# Encoder.net
KiCad netlist of a schematic drawn in EAGLE
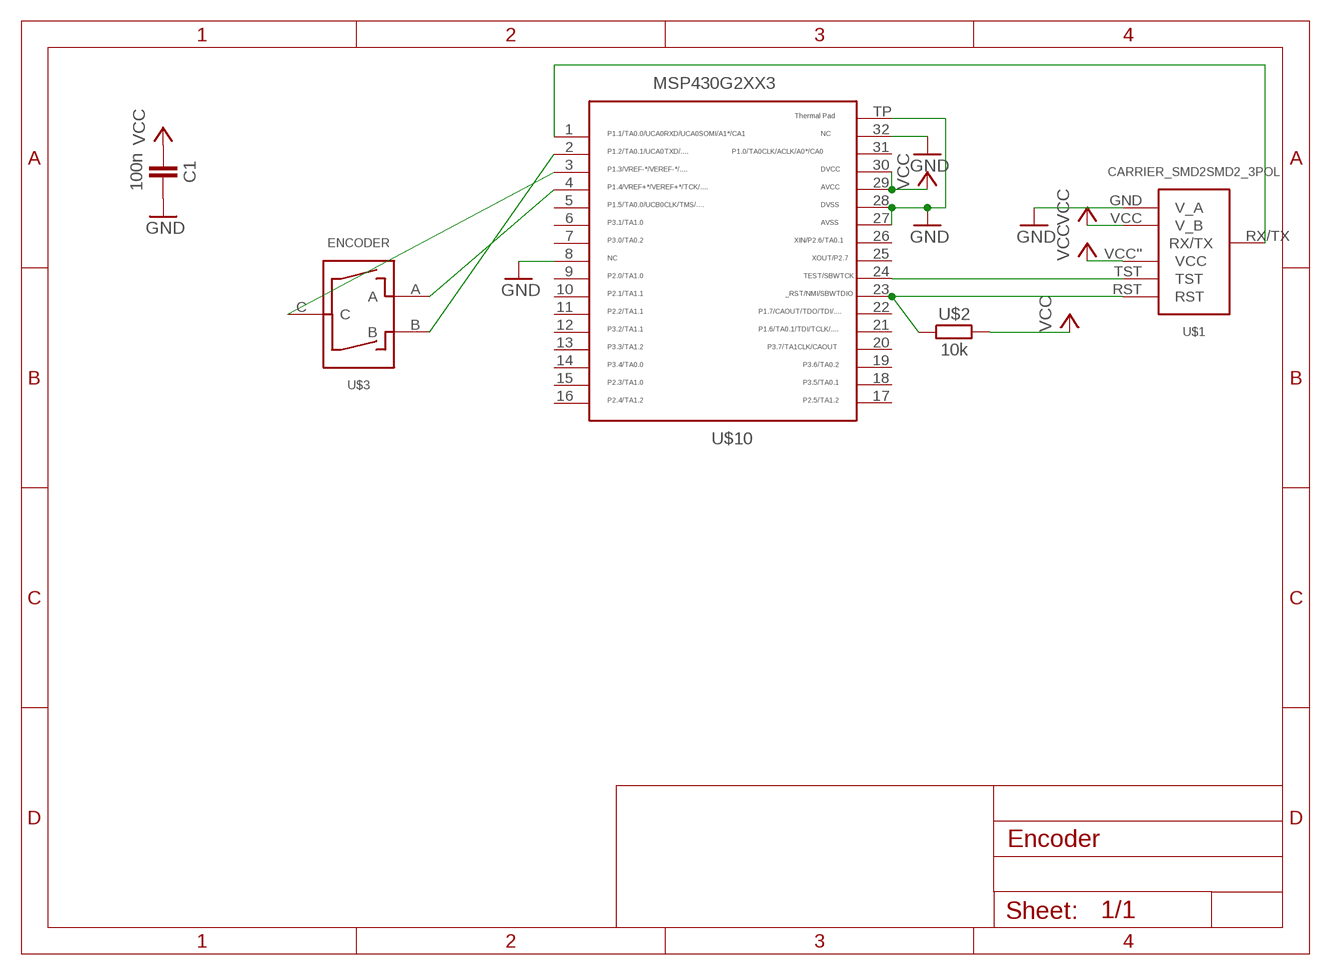
[diagram p0: schematic, sheet 1]

(export (version "E")
  (design (tool "Eeschema 10.0.6"))
  (components
    (comp (ref "C1")
      (value "100n")
      (footprint "eagle-import:603")
      (libsource (lib "eagle-import") (part "CAPACITOR"))
    )
    (comp (ref "U$1")
      (value "CARRIER_SMD2SMD2_3POL")
      (footprint "eagle-import:CARRIER_SMD2_3POL")
      (libsource (lib "eagle-import") (part "CARRIER_SMD2SMD2_3POL"))
    )
    (comp (ref "U$2")
      (value "10k")
      (footprint "eagle-import:603")
      (libsource (lib "eagle-import") (part "RESISTOR0603"))
    )
    (comp (ref "U$3")
      (value "ENCODER")
      (footprint "eagle-import:EC05E")
      (libsource (lib "eagle-import") (part "ENCODER"))
    )
    (comp (ref "U$10")
      (value "MSP430G2553")
      (footprint "eagle-import:QFN32")
      (libsource (lib "eagle-import") (part "MSP430G2553"))
    )
  )
  (nets
    (net (code "1") (name "GND") (class "Default")
      (node (ref "C1") (pin "2") (pinfunction "2_2") (pintype "passive"))
      (node (ref "U$1") (pin "GND") (pinfunction "V_A_GND") (pintype "bidirectional"))
      (node (ref "U$10") (pin "27") (pinfunction "27_27") (pintype "bidirectional"))
      (node (ref "U$10") (pin "28") (pinfunction "28_28") (pintype "bidirectional"))
      (node (ref "U$10") (pin "32") (pinfunction "32_32") (pintype "bidirectional"))
      (node (ref "U$10") (pin "8") (pinfunction "8_8") (pintype "bidirectional"))
      (node (ref "U$10") (pin "TP") (pinfunction "TP_TP") (pintype "bidirectional"))
    )
    (net (code "2") (name "Net-(U$1-PadRST)") (class "Default")
      (node (ref "U$1") (pin "RST") (pinfunction "RST_RST") (pintype "bidirectional"))
      (node (ref "U$10") (pin "23") (pinfunction "23_23") (pintype "bidirectional"))
      (node (ref "U$2") (pin "1") (pinfunction "1_1") (pintype "passive"))
    )
    (net (code "3") (name "Net-(U$1-PadRX{slash}TX)") (class "Default")
      (node (ref "U$1") (pin "RX/TX") (pinfunction "RX/TX_RX/TX") (pintype "bidirectional"))
      (node (ref "U$10") (pin "1") (pinfunction "1_1") (pintype "bidirectional"))
    )
    (net (code "4") (name "Net-(U$1-PadTST)") (class "Default")
      (node (ref "U$1") (pin "TST") (pinfunction "TST_TST") (pintype "bidirectional"))
      (node (ref "U$10") (pin "24") (pinfunction "24_24") (pintype "bidirectional"))
    )
    (net (code "5") (name "Net-(U$10-Pad2)") (class "Default")
      (node (ref "U$10") (pin "2") (pinfunction "2_2") (pintype "bidirectional"))
      (node (ref "U$3") (pin "B") (pinfunction "B_B") (pintype "bidirectional"))
    )
    (net (code "6") (name "Net-(U$10-Pad3)") (class "Default")
      (node (ref "U$10") (pin "3") (pinfunction "3_3") (pintype "bidirectional"))
      (node (ref "U$3") (pin "C") (pinfunction "C_C") (pintype "bidirectional"))
    )
    (net (code "7") (name "Net-(U$10-Pad4)") (class "Default")
      (node (ref "U$10") (pin "4") (pinfunction "4_4") (pintype "bidirectional"))
      (node (ref "U$3") (pin "A") (pinfunction "A_A") (pintype "bidirectional"))
    )
    (net (code "8") (name "VCC") (class "Default")
      (node (ref "C1") (pin "1") (pinfunction "1_1") (pintype "passive"))
      (node (ref "U$1") (pin "VCC") (pinfunction "V_B_VCC") (pintype "bidirectional"))
      (node (ref "U$1") (pin "VCC''") (pinfunction "VCC_VCC''") (pintype "bidirectional"))
      (node (ref "U$10") (pin "29") (pinfunction "29_29") (pintype "bidirectional"))
      (node (ref "U$10") (pin "30") (pinfunction "30_30") (pintype "bidirectional"))
      (node (ref "U$2") (pin "2") (pinfunction "2_2") (pintype "passive"))
    )
    (net (code "9") (name "unconnected-(U$10-Pad5)") (class "Default")
      (node (ref "U$10") (pin "5") (pinfunction "5_5") (pintype "bidirectional"))
    )
    (net (code "10") (name "unconnected-(U$10-Pad6)") (class "Default")
      (node (ref "U$10") (pin "6") (pinfunction "6_6") (pintype "bidirectional"))
    )
    (net (code "11") (name "unconnected-(U$10-Pad7)") (class "Default")
      (node (ref "U$10") (pin "7") (pinfunction "7_7") (pintype "bidirectional"))
    )
    (net (code "12") (name "unconnected-(U$10-Pad9)") (class "Default")
      (node (ref "U$10") (pin "9") (pinfunction "9_9") (pintype "bidirectional"))
    )
    (net (code "13") (name "unconnected-(U$10-Pad10)") (class "Default")
      (node (ref "U$10") (pin "10") (pinfunction "10_10") (pintype "bidirectional"))
    )
    (net (code "14") (name "unconnected-(U$10-Pad11)") (class "Default")
      (node (ref "U$10") (pin "11") (pinfunction "11_11") (pintype "bidirectional"))
    )
    (net (code "15") (name "unconnected-(U$10-Pad12)") (class "Default")
      (node (ref "U$10") (pin "12") (pinfunction "12_12") (pintype "bidirectional"))
    )
    (net (code "16") (name "unconnected-(U$10-Pad13)") (class "Default")
      (node (ref "U$10") (pin "13") (pinfunction "13_13") (pintype "bidirectional"))
    )
    (net (code "17") (name "unconnected-(U$10-Pad14)") (class "Default")
      (node (ref "U$10") (pin "14") (pinfunction "14_14") (pintype "bidirectional"))
    )
    (net (code "18") (name "unconnected-(U$10-Pad15)") (class "Default")
      (node (ref "U$10") (pin "15") (pinfunction "15_15") (pintype "bidirectional"))
    )
    (net (code "19") (name "unconnected-(U$10-Pad16)") (class "Default")
      (node (ref "U$10") (pin "16") (pinfunction "16_16") (pintype "bidirectional"))
    )
    (net (code "20") (name "unconnected-(U$10-Pad17)") (class "Default")
      (node (ref "U$10") (pin "17") (pinfunction "17_17") (pintype "bidirectional"))
    )
    (net (code "21") (name "unconnected-(U$10-Pad18)") (class "Default")
      (node (ref "U$10") (pin "18") (pinfunction "18_18") (pintype "bidirectional"))
    )
    (net (code "22") (name "unconnected-(U$10-Pad19)") (class "Default")
      (node (ref "U$10") (pin "19") (pinfunction "19_19") (pintype "bidirectional"))
    )
    (net (code "23") (name "unconnected-(U$10-Pad20)") (class "Default")
      (node (ref "U$10") (pin "20") (pinfunction "20_20") (pintype "bidirectional"))
    )
    (net (code "24") (name "unconnected-(U$10-Pad21)") (class "Default")
      (node (ref "U$10") (pin "21") (pinfunction "21_21") (pintype "bidirectional"))
    )
    (net (code "25") (name "unconnected-(U$10-Pad22)") (class "Default")
      (node (ref "U$10") (pin "22") (pinfunction "22_22") (pintype "bidirectional"))
    )
    (net (code "26") (name "unconnected-(U$10-Pad25)") (class "Default")
      (node (ref "U$10") (pin "25") (pinfunction "25_25") (pintype "bidirectional"))
    )
    (net (code "27") (name "unconnected-(U$10-Pad26)") (class "Default")
      (node (ref "U$10") (pin "26") (pinfunction "26_26") (pintype "bidirectional"))
    )
    (net (code "28") (name "unconnected-(U$10-Pad31)") (class "Default")
      (node (ref "U$10") (pin "31") (pinfunction "31_31") (pintype "bidirectional"))
    )
  )
)
